# 18_USB2_USB3.net
KiCad netlist of a schematic drawn in Altium Designer
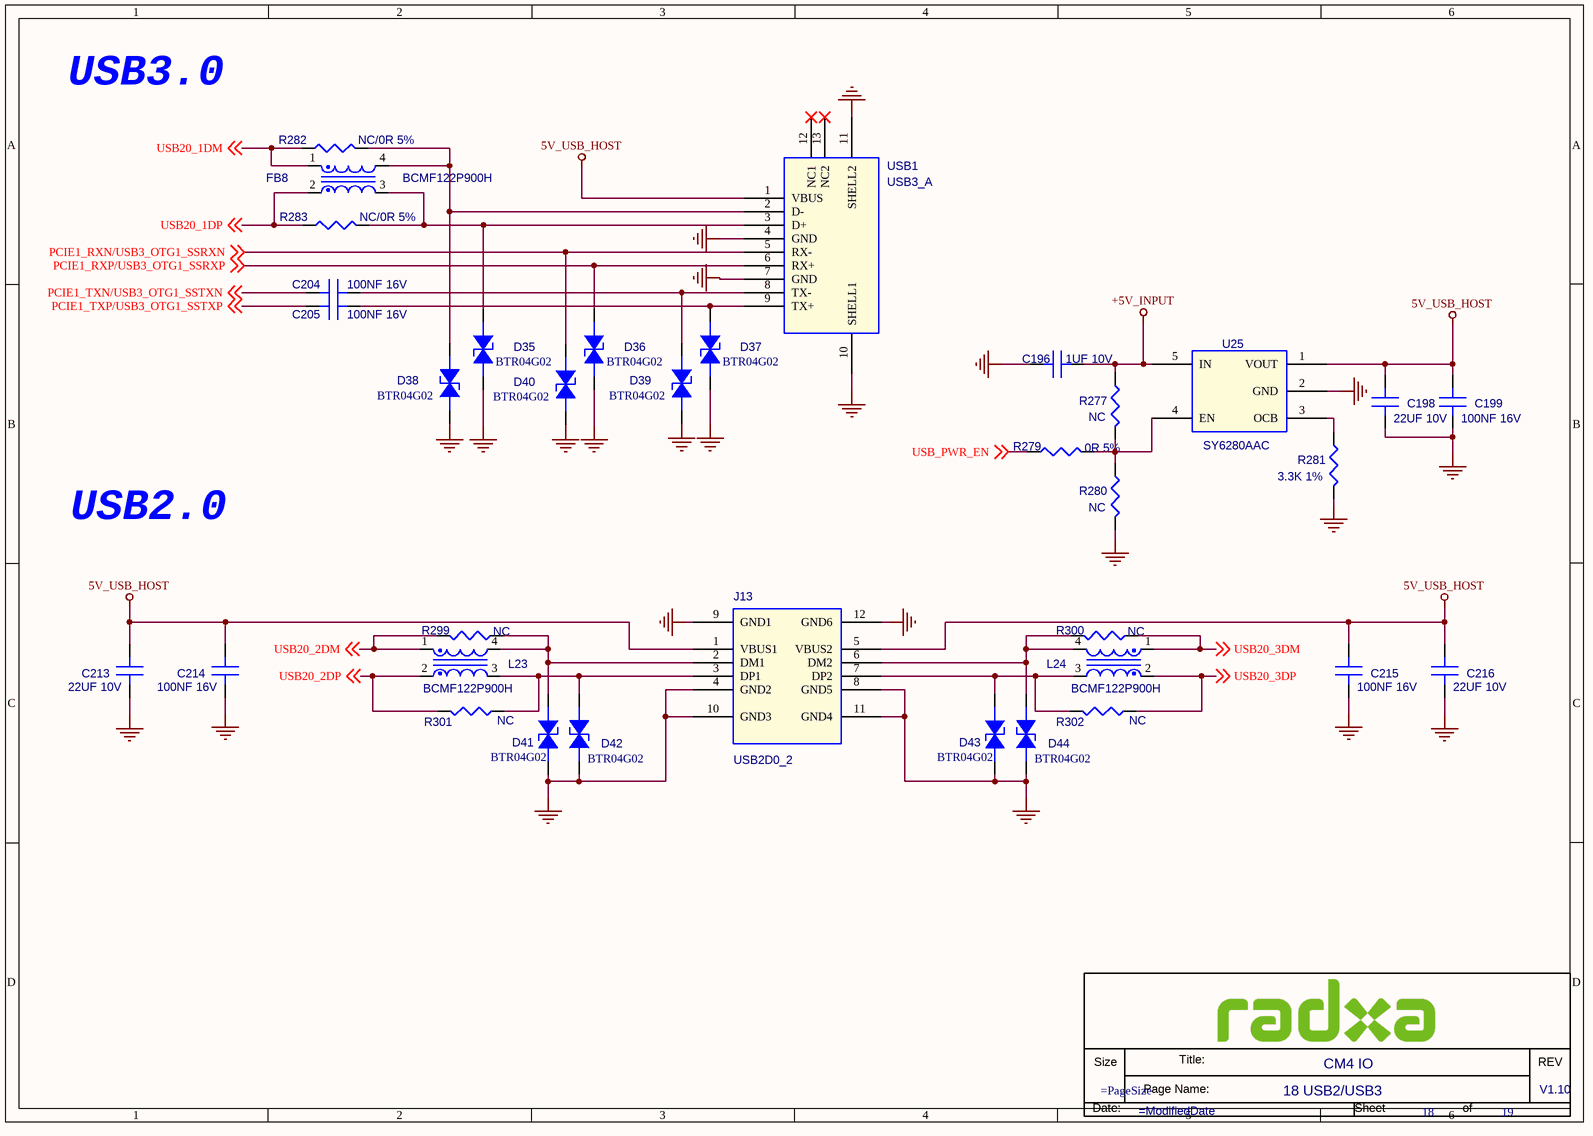
[diagram p0: 18 USB2_USB3.SchDoc]

(export (version "E")
  (design (tool "Eeschema 10.0.6"))
  (components
    (comp (ref "C196")
      (value "1UF 10V")
      (footprint "C0201")
      (description "SMD  0201  1UF  10V  X5R  ±20%  ROHS")
      (fields (field (name "PART NUMBER") "A1C01.00081"))
      (libsource (lib "*") (part "C"))
    )
    (comp (ref "C198")
      (value "22UF 10V")
      (footprint "C0603")
      (description "SMD  0603  22UF  10V  X5R  ±20%  ROHS")
      (fields (field (name "PART NUMBER") "A1C01.00015"))
      (libsource (lib "*") (part "C"))
    )
    (comp (ref "C199")
      (value "100NF 16V")
      (footprint "C0201")
      (description "SMD  0201  100NF  16V  X5R  ±20%  ROHS")
      (fields (field (name "PART NUMBER") "A1C01.00099"))
      (libsource (lib "*") (part "C"))
    )
    (comp (ref "C204")
      (value "100NF 16V")
      (footprint "C0201")
      (description "SMD  0201  100NF  16V  X5R  ±20%  ROHS")
      (fields (field (name "PART NUMBER") "A1C01.00099"))
      (libsource (lib "*") (part "C"))
    )
    (comp (ref "C205")
      (value "100NF 16V")
      (footprint "C0201")
      (description "SMD  0201  100NF  16V  X5R  ±20%  ROHS")
      (fields (field (name "PART NUMBER") "A1C01.00099"))
      (libsource (lib "*") (part "C"))
    )
    (comp (ref "C213")
      (value "22UF 10V")
      (footprint "C0603")
      (description "SMD  0603  22UF  10V  X5R  ±20%  ROHS")
      (fields (field (name "PART NUMBER") "A1C01.00015"))
      (libsource (lib "*") (part "C"))
    )
    (comp (ref "C214")
      (value "100NF 16V")
      (footprint "C0201")
      (description "SMD  0201  100NF  16V  X5R  ±20%  ROHS")
      (fields (field (name "PART NUMBER") "A1C01.00099"))
      (libsource (lib "*") (part "C"))
    )
    (comp (ref "C215")
      (value "100NF 16V")
      (footprint "C0201")
      (description "SMD  0201  100NF  16V  X5R  ±20%  ROHS")
      (fields (field (name "PART NUMBER") "A1C01.00099"))
      (libsource (lib "*") (part "C"))
    )
    (comp (ref "C216")
      (value "22UF 10V")
      (footprint "C0603")
      (description "SMD  0603  22UF  10V  X5R  ±20%  ROHS")
      (fields (field (name "PART NUMBER") "A1C01.00015"))
      (libsource (lib "*") (part "C"))
    )
    (comp (ref "D35")
      (value "BTR04G02")
      (footprint "DFN1006-2L")
      (description "SMD  编带  0402  BTR04G02  B-tron  ROHS")
      (fields (field (name "PART NUMBER") "A1D02.00002"))
      (libsource (lib "*") (part "ESD"))
    )
    (comp (ref "D36")
      (value "BTR04G02")
      (footprint "DFN1006-2L")
      (description "SMD  编带  0402  BTR04G02  B-tron  ROHS")
      (fields (field (name "PART NUMBER") "A1D02.00002"))
      (libsource (lib "*") (part "ESD"))
    )
    (comp (ref "D37")
      (value "BTR04G02")
      (footprint "DFN1006-2L")
      (description "SMD  编带  0402  BTR04G02  B-tron  ROHS")
      (fields (field (name "PART NUMBER") "A1D02.00002"))
      (libsource (lib "*") (part "ESD"))
    )
    (comp (ref "D38")
      (value "BTR04G02")
      (footprint "DFN1006-2L")
      (description "SMD  编带  0402  BTR04G02  B-tron  ROHS")
      (fields (field (name "PART NUMBER") "A1D02.00002"))
      (libsource (lib "*") (part "ESD"))
    )
    (comp (ref "D39")
      (value "BTR04G02")
      (footprint "DFN1006-2L")
      (description "SMD  编带  0402  BTR04G02  B-tron  ROHS")
      (fields (field (name "PART NUMBER") "A1D02.00002"))
      (libsource (lib "*") (part "ESD"))
    )
    (comp (ref "D40")
      (value "BTR04G02")
      (footprint "DFN1006-2L")
      (description "SMD  编带  0402  BTR04G02  B-tron  ROHS")
      (fields (field (name "PART NUMBER") "A1D02.00002"))
      (libsource (lib "*") (part "ESD"))
    )
    (comp (ref "D41")
      (value "BTR04G02")
      (footprint "DFN1006-2L")
      (description "SMD  编带  0402  BTR04G02  B-tron  ROHS")
      (fields (field (name "PART NUMBER") "A1D02.00002"))
      (libsource (lib "*") (part "ESD"))
    )
    (comp (ref "D42")
      (value "BTR04G02")
      (footprint "DFN1006-2L")
      (description "SMD  编带  0402  BTR04G02  B-tron  ROHS")
      (fields (field (name "PART NUMBER") "A1D02.00002"))
      (libsource (lib "*") (part "ESD"))
    )
    (comp (ref "D43")
      (value "BTR04G02")
      (footprint "DFN1006-2L")
      (description "SMD  编带  0402  BTR04G02  B-tron  ROHS")
      (fields (field (name "PART NUMBER") "A1D02.00002"))
      (libsource (lib "*") (part "ESD"))
    )
    (comp (ref "D44")
      (value "BTR04G02")
      (footprint "DFN1006-2L")
      (description "SMD  编带  0402  BTR04G02  B-tron  ROHS")
      (fields (field (name "PART NUMBER") "A1D02.00002"))
      (libsource (lib "*") (part "ESD"))
    )
    (comp (ref "FB8")
      (value "BCMF122P900H")
      (footprint "LC1210")
      (description "SMD  BCMF122P900H  90R  4PIN  不带ESD  ±5%  B-tron  ROHS")
      (fields (field (name "PART NUMBER") "A1L03.00003"))
      (libsource (lib "*") (part "MCZ1210AH900L2"))
    )
    (comp (ref "J13")
      (value "USB2D0_2")
      (footprint "CON_USB2D0_TH1X2_LIE")
      (fields (field (name "PART NUMBER") "A1J08.00050"))
      (libsource (lib "*") (part "USB2D0_2"))
    )
    (comp (ref "L23")
      (value "BCMF122P900H")
      (footprint "LC1210")
      (description "SMD  BCMF122P900H  90R  4PIN  不带ESD  ±5%  B-tron  ROHS")
      (fields (field (name "PART NUMBER") "A1L03.00003"))
      (libsource (lib "*") (part "MCZ1210AH900L2"))
    )
    (comp (ref "L24")
      (value "BCMF122P900H")
      (footprint "LC1210")
      (description "SMD  BCMF122P900H  90R  4PIN  不带ESD  ±5%  B-tron  ROHS")
      (fields (field (name "PART NUMBER") "A1L03.00003"))
      (libsource (lib "") (part "MCZ1210AH900L2_1"))
    )
    (comp (ref "R277")
      (value "NC")
      (footprint "R0402")
      (description "SMD  0201  6.8K  1/20W  ±1%  ROHS")
      (fields (field (name "PART NUMBER") "A1R01.00158"))
      (libsource (lib "*") (part "R"))
    )
    (comp (ref "R279")
      (value "0R 5%")
      (footprint "R0402")
      (description "SMD  0201  1K  1/20W  ±5%  ROHS")
      (fields (field (name "PART NUMBER") "A1R01.00018"))
      (libsource (lib "*") (part "R"))
    )
    (comp (ref "R280")
      (value "NC")
      (footprint "R0402")
      (description "SMD  0201  6.8K  1/20W  ±1%  ROHS")
      (fields (field (name "PART NUMBER") "A1R01.00158"))
      (libsource (lib "*") (part "R"))
    )
    (comp (ref "R281")
      (value "3.3K 1%")
      (footprint "R0402")
      (description "SMD  0201  3.3K  1/20W  ±1%  ROHS")
      (fields (field (name "PART NUMBER") "A1R01.00178"))
      (libsource (lib "*") (part "R"))
    )
    (comp (ref "R282")
      (value "NC/0R 5%")
      (footprint "R0402")
      (description "SMD  0201  0R  1/20W  ±5%  ROHS")
      (fields (field (name "PART NUMBER") "A1R01.00027"))
      (libsource (lib "*") (part "R"))
    )
    (comp (ref "R283")
      (value "NC/0R 5%")
      (footprint "R0402")
      (description "SMD  0201  0R  1/20W  ±5%  ROHS")
      (fields (field (name "PART NUMBER") "A1R01.00027"))
      (libsource (lib "*") (part "R"))
    )
    (comp (ref "R299")
      (value "NC")
      (footprint "R0402")
      (description "SMD  0201  0R  1/20W  ±5%  ROHS")
      (fields (field (name "PART NUMBER") "A1R01.00027"))
      (libsource (lib "*") (part "R"))
    )
    (comp (ref "R300")
      (value "NC")
      (footprint "R0402")
      (description "SMD  0201  0R  1/20W  ±5%  ROHS")
      (fields (field (name "PART NUMBER") "A1R01.00027"))
      (libsource (lib "*") (part "R"))
    )
    (comp (ref "R301")
      (value "NC")
      (footprint "R0402")
      (description "SMD  0201  0R  1/20W  ±5%  ROHS")
      (fields (field (name "PART NUMBER") "A1R01.00027"))
      (libsource (lib "*") (part "R"))
    )
    (comp (ref "R302")
      (value "NC")
      (footprint "R0402")
      (description "SMD  0201  0R  1/20W  ±5%  ROHS")
      (fields (field (name "PART NUMBER") "A1R01.00027"))
      (libsource (lib "*") (part "R"))
    )
    (comp (ref "U25")
      (value "SY6280AAC")
      (footprint "SOT23_5")
      (description "SMD  USB限流  SY6280AAC  SOT23-5  silergy(矽力杰)  ROHS")
      (fields (field (name "PART NUMBER") "A1I01.00017"))
      (libsource (lib "*") (part "SY6280"))
    )
    (comp (ref "USB1")
      (value "USB3_A")
      (footprint "USB_SM9_2D0_LIE")
      (fields (field (name "PART NUMBER") "A1J08.00010"))
      (libsource (lib "*") (part "USB3_A"))
    )
  )
  (nets
    (net (code "1") (name "+5V_INPUT") (class "Default")
      (node (ref "C196") (pin "1") (pinfunction "A_1") (pintype "passive"))
      (node (ref "R277") (pin "1") (pinfunction "1_1") (pintype "passive"))
      (node (ref "U25") (pin "5") (pinfunction "IN_5") (pintype "passive"))
    )
    (net (code "2") (name "5V_USB_HOST") (class "Default")
      (node (ref "C198") (pin "1") (pinfunction "A_1") (pintype "passive"))
      (node (ref "C199") (pin "1") (pinfunction "A_1") (pintype "passive"))
      (node (ref "C213") (pin "1") (pinfunction "A_1") (pintype "passive"))
      (node (ref "C214") (pin "1") (pinfunction "A_1") (pintype "passive"))
      (node (ref "C215") (pin "1") (pinfunction "A_1") (pintype "passive"))
      (node (ref "C216") (pin "1") (pinfunction "A_1") (pintype "passive"))
      (node (ref "J13") (pin "1") (pinfunction "VBUS1_1") (pintype "passive"))
      (node (ref "J13") (pin "5") (pinfunction "VBUS2_5") (pintype "passive"))
      (node (ref "U25") (pin "1") (pinfunction "VOUT_1") (pintype "passive"))
      (node (ref "USB1") (pin "1") (pinfunction "VBUS_1") (pintype "power_in"))
    )
    (net (code "3") (name "GND") (class "Default")
      (node (ref "C196") (pin "2") (pinfunction "B_2") (pintype "passive"))
      (node (ref "C198") (pin "2") (pinfunction "B_2") (pintype "passive"))
      (node (ref "C199") (pin "2") (pinfunction "B_2") (pintype "passive"))
      (node (ref "C213") (pin "2") (pinfunction "B_2") (pintype "passive"))
      (node (ref "C214") (pin "2") (pinfunction "B_2") (pintype "passive"))
      (node (ref "C215") (pin "2") (pinfunction "B_2") (pintype "passive"))
      (node (ref "C216") (pin "2") (pinfunction "B_2") (pintype "passive"))
      (node (ref "D35") (pin "1") (pinfunction "ANODE_1") (pintype "passive"))
      (node (ref "D36") (pin "1") (pinfunction "ANODE_1") (pintype "passive"))
      (node (ref "D37") (pin "1") (pinfunction "ANODE_1") (pintype "passive"))
      (node (ref "D38") (pin "1") (pinfunction "ANODE_1") (pintype "passive"))
      (node (ref "D39") (pin "1") (pinfunction "ANODE_1") (pintype "passive"))
      (node (ref "D40") (pin "1") (pinfunction "ANODE_1") (pintype "passive"))
      (node (ref "D41") (pin "1") (pinfunction "ANODE_1") (pintype "passive"))
      (node (ref "D42") (pin "1") (pinfunction "ANODE_1") (pintype "passive"))
      (node (ref "D43") (pin "1") (pinfunction "ANODE_1") (pintype "passive"))
      (node (ref "D44") (pin "1") (pinfunction "ANODE_1") (pintype "passive"))
      (node (ref "J13") (pin "10") (pinfunction "GND3_10") (pintype "passive"))
      (node (ref "J13") (pin "11") (pinfunction "GND4_11") (pintype "passive"))
      (node (ref "J13") (pin "12") (pinfunction "GND6_12") (pintype "passive"))
      (node (ref "J13") (pin "4") (pinfunction "GND2_4") (pintype "passive"))
      (node (ref "J13") (pin "8") (pinfunction "GND5_8") (pintype "passive"))
      (node (ref "J13") (pin "9") (pinfunction "GND1_9") (pintype "passive"))
      (node (ref "R280") (pin "2") (pinfunction "2_2") (pintype "passive"))
      (node (ref "R281") (pin "2") (pinfunction "2_2") (pintype "passive"))
      (node (ref "U25") (pin "2") (pinfunction "GND_2") (pintype "passive"))
      (node (ref "USB1") (pin "10") (pinfunction "SHELL1_10") (pintype "passive"))
      (node (ref "USB1") (pin "11") (pinfunction "SHELL2_11") (pintype "passive"))
      (node (ref "USB1") (pin "4") (pinfunction "GND_4") (pintype "power_in"))
      (node (ref "USB1") (pin "7") (pinfunction "GND_7") (pintype "power_in"))
    )
    (net (code "4") (name "Net-(C204-B)") (class "Default")
      (node (ref "C204") (pin "2") (pinfunction "B_2") (pintype "passive"))
      (node (ref "D39") (pin "2") (pinfunction "CATHODE_2") (pintype "passive"))
      (node (ref "USB1") (pin "8") (pinfunction "TX-_8") (pintype "passive"))
    )
    (net (code "5") (name "Net-(C205-B)") (class "Default")
      (node (ref "C205") (pin "2") (pinfunction "B_2") (pintype "passive"))
      (node (ref "D37") (pin "2") (pinfunction "CATHODE_2") (pintype "passive"))
      (node (ref "USB1") (pin "9") (pinfunction "TX+_9") (pintype "passive"))
    )
    (net (code "6") (name "Net-(D35-CATHODE)") (class "Default")
      (node (ref "D35") (pin "2") (pinfunction "CATHODE_2") (pintype "passive"))
      (node (ref "FB8") (pin "3") (pinfunction "3_3") (pintype "passive"))
      (node (ref "R283") (pin "1") (pinfunction "1_1") (pintype "passive"))
      (node (ref "USB1") (pin "3") (pinfunction "D+_3") (pintype "passive"))
    )
    (net (code "7") (name "Net-(D38-CATHODE)") (class "Default")
      (node (ref "D38") (pin "2") (pinfunction "CATHODE_2") (pintype "passive"))
      (node (ref "FB8") (pin "4") (pinfunction "4_4") (pintype "passive"))
      (node (ref "R282") (pin "1") (pinfunction "1_1") (pintype "passive"))
      (node (ref "USB1") (pin "2") (pinfunction "D-_2") (pintype "passive"))
    )
    (net (code "8") (name "Net-(D41-CATHODE)") (class "Default")
      (node (ref "D41") (pin "2") (pinfunction "CATHODE_2") (pintype "passive"))
      (node (ref "J13") (pin "2") (pinfunction "DM1_2") (pintype "passive"))
      (node (ref "L23") (pin "4") (pinfunction "4_4") (pintype "passive"))
      (node (ref "R299") (pin "2") (pinfunction "2_2") (pintype "passive"))
    )
    (net (code "9") (name "Net-(D42-CATHODE)") (class "Default")
      (node (ref "D42") (pin "2") (pinfunction "CATHODE_2") (pintype "passive"))
      (node (ref "J13") (pin "3") (pinfunction "DP1_3") (pintype "passive"))
      (node (ref "L23") (pin "3") (pinfunction "3_3") (pintype "passive"))
      (node (ref "R301") (pin "2") (pinfunction "2_2") (pintype "passive"))
    )
    (net (code "10") (name "Net-(D43-CATHODE)") (class "Default")
      (node (ref "D43") (pin "2") (pinfunction "CATHODE_2") (pintype "passive"))
      (node (ref "J13") (pin "7") (pinfunction "DP2_7") (pintype "passive"))
      (node (ref "L24") (pin "3") (pinfunction "3_3") (pintype "passive"))
      (node (ref "R302") (pin "2") (pinfunction "2_2") (pintype "passive"))
    )
    (net (code "11") (name "Net-(D44-CATHODE)") (class "Default")
      (node (ref "D44") (pin "2") (pinfunction "CATHODE_2") (pintype "passive"))
      (node (ref "J13") (pin "6") (pinfunction "DM2_6") (pintype "passive"))
      (node (ref "L24") (pin "4") (pinfunction "4_4") (pintype "passive"))
      (node (ref "R300") (pin "2") (pinfunction "2_2") (pintype "passive"))
    )
    (net (code "12") (name "Net-(U25-EN)") (class "Default")
      (node (ref "R277") (pin "2") (pinfunction "2_2") (pintype "passive"))
      (node (ref "R279") (pin "1") (pinfunction "1_1") (pintype "passive"))
      (node (ref "R280") (pin "1") (pinfunction "1_1") (pintype "passive"))
      (node (ref "U25") (pin "4") (pinfunction "EN_4") (pintype "passive"))
    )
    (net (code "13") (name "Net-(U25-OCB)") (class "Default")
      (node (ref "R281") (pin "1") (pinfunction "1_1") (pintype "passive"))
      (node (ref "U25") (pin "3") (pinfunction "OCB_3") (pintype "passive"))
    )
    (net (code "14") (name "PCIE1_RXN{slash}USB3_OTG1_SSRXN") (class "Default")
      (node (ref "D40") (pin "2") (pinfunction "CATHODE_2") (pintype "passive"))
      (node (ref "USB1") (pin "5") (pinfunction "RX-_5") (pintype "passive"))
    )
    (net (code "15") (name "PCIE1_RXP{slash}USB3_OTG1_SSRXP") (class "Default")
      (node (ref "D36") (pin "2") (pinfunction "CATHODE_2") (pintype "passive"))
      (node (ref "USB1") (pin "6") (pinfunction "RX+_6") (pintype "passive"))
    )
    (net (code "16") (name "PCIE1_TXN{slash}USB3_OTG1_SSTXN") (class "Default")
      (node (ref "C204") (pin "1") (pinfunction "A_1") (pintype "passive"))
    )
    (net (code "17") (name "PCIE1_TXP{slash}USB3_OTG1_SSTXP") (class "Default")
      (node (ref "C205") (pin "1") (pinfunction "A_1") (pintype "passive"))
    )
    (net (code "18") (name "USB20_1DM") (class "Default")
      (node (ref "FB8") (pin "1") (pinfunction "1_1") (pintype "passive"))
      (node (ref "R282") (pin "2") (pinfunction "2_2") (pintype "passive"))
    )
    (net (code "19") (name "USB20_1DP") (class "Default")
      (node (ref "FB8") (pin "2") (pinfunction "2_2") (pintype "passive"))
      (node (ref "R283") (pin "2") (pinfunction "2_2") (pintype "passive"))
    )
    (net (code "20") (name "USB20_2DM") (class "Default")
      (node (ref "L23") (pin "1") (pinfunction "1_1") (pintype "passive"))
      (node (ref "R299") (pin "1") (pinfunction "1_1") (pintype "passive"))
    )
    (net (code "21") (name "USB20_2DP") (class "Default")
      (node (ref "L23") (pin "2") (pinfunction "2_2") (pintype "passive"))
      (node (ref "R301") (pin "1") (pinfunction "1_1") (pintype "passive"))
    )
    (net (code "22") (name "USB20_3DM") (class "Default")
      (node (ref "L24") (pin "1") (pinfunction "1_1") (pintype "passive"))
      (node (ref "R300") (pin "1") (pinfunction "1_1") (pintype "passive"))
    )
    (net (code "23") (name "USB20_3DP") (class "Default")
      (node (ref "L24") (pin "2") (pinfunction "2_2") (pintype "passive"))
      (node (ref "R302") (pin "1") (pinfunction "1_1") (pintype "passive"))
    )
    (net (code "24") (name "USB_PWR_EN") (class "Default")
      (node (ref "R279") (pin "2") (pinfunction "2_2") (pintype "passive"))
    )
    (net (code "25") (name "unconnected-(USB1-NC1-Pad12)") (class "Default")
      (node (ref "USB1") (pin "12") (pinfunction "NC1_12") (pintype "passive+no_connect"))
    )
    (net (code "26") (name "unconnected-(USB1-NC2-Pad13)") (class "Default")
      (node (ref "USB1") (pin "13") (pinfunction "NC2_13") (pintype "passive+no_connect"))
    )
  )
)
